# lsm9ds0-breakout.net
KiCad netlist of a schematic drawn in EAGLE
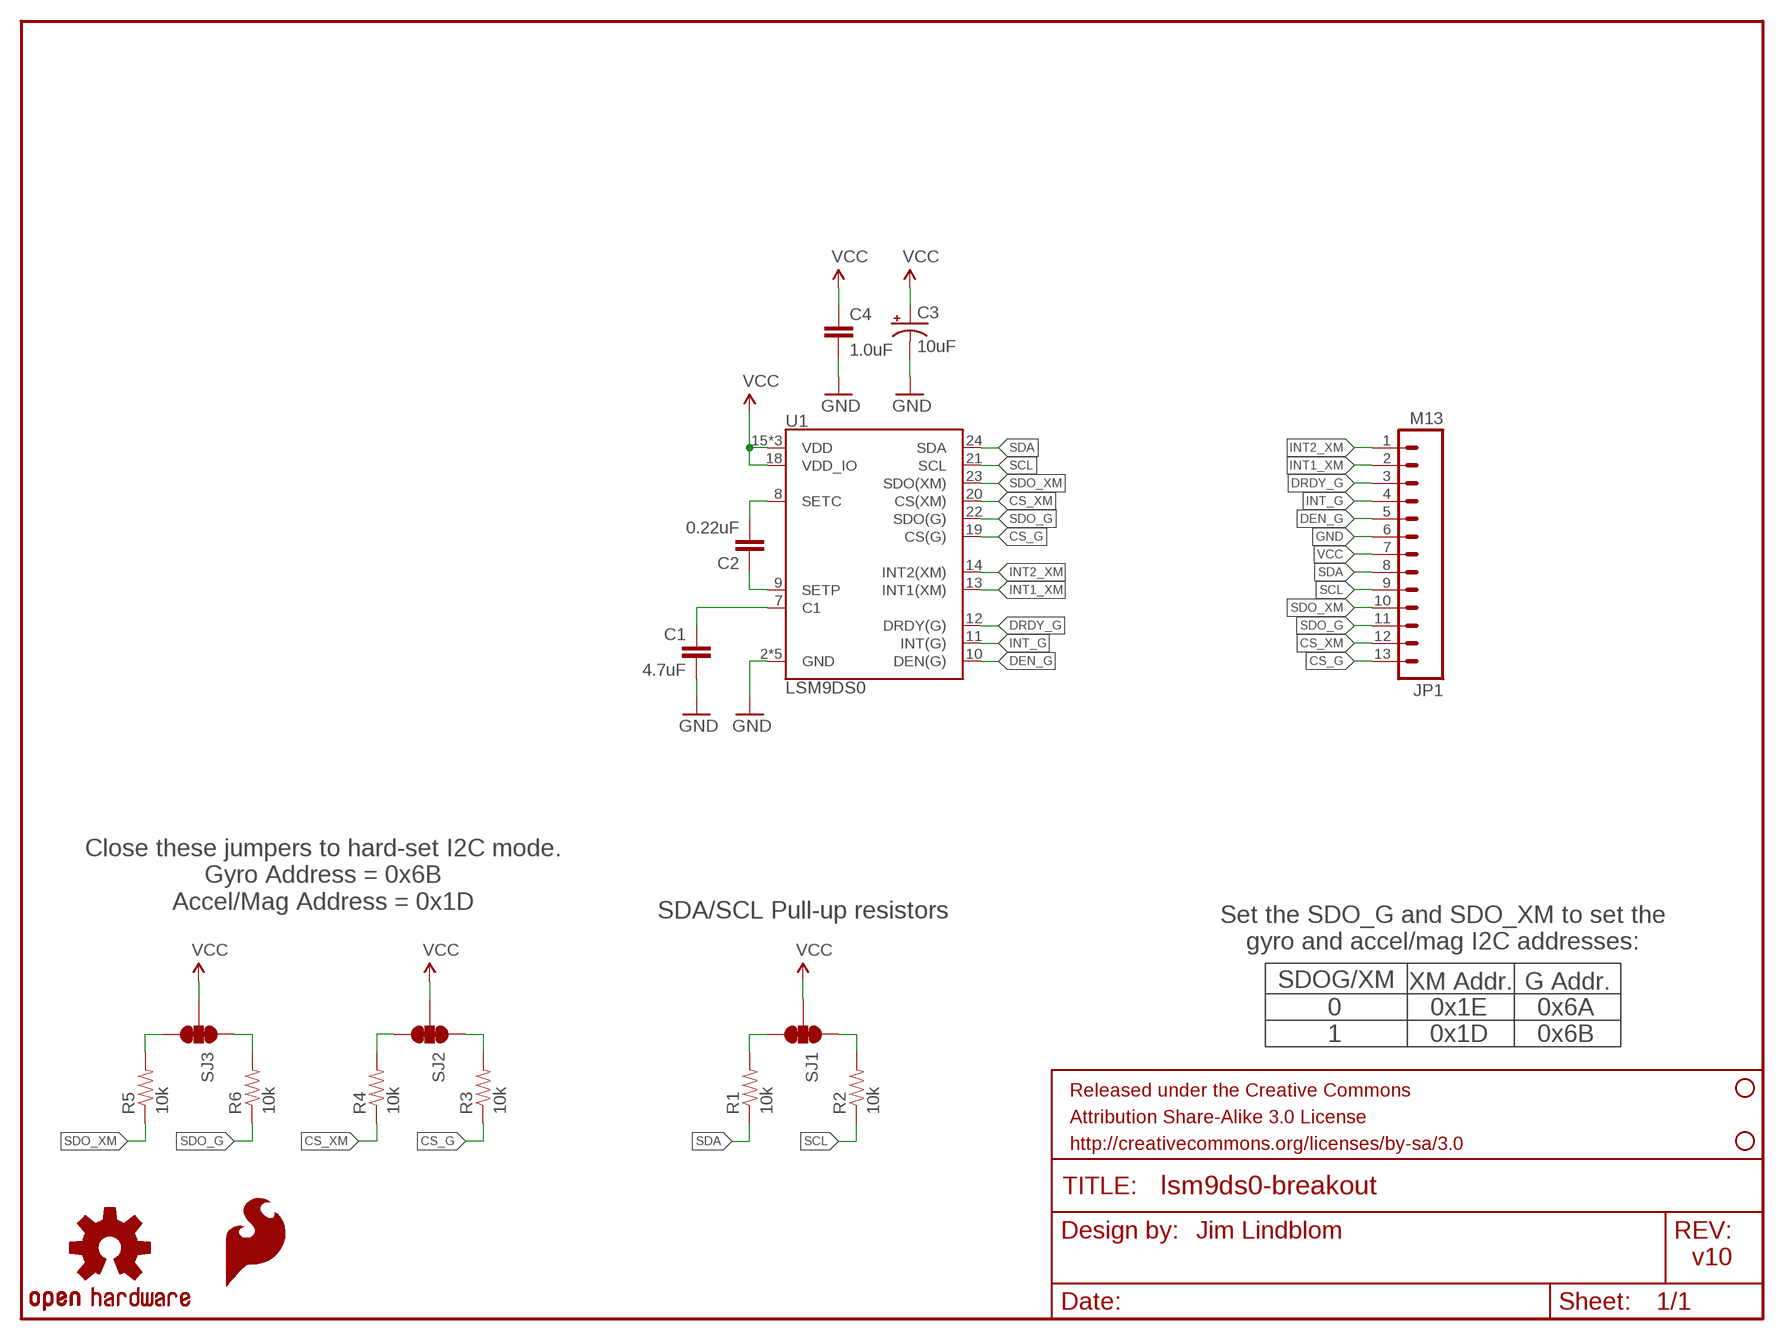
[diagram p0: schematic, sheet 1]

(export (version "E")
  (design (tool "Eeschema 10.0.6"))
  (components
    (comp (ref "C1")
      (value "4.7uF")
      (footprint "eagle-import:0603-CAP")
      (libsource (lib "eagle-import") (part "4.7UF-6.3V-10%(0603)0603"))
    )
    (comp (ref "C2")
      (value "0.22uF")
      (footprint "eagle-import:0603-CAP")
      (libsource (lib "eagle-import") (part "0.22UF-25V-10%(0603)"))
    )
    (comp (ref "C3")
      (value "10uF")
      (footprint "eagle-import:EIA3216")
      (libsource (lib "eagle-import") (part "10UF-16V-10%(TANT)"))
    )
    (comp (ref "C4")
      (value "1.0uF")
      (footprint "eagle-import:0603-CAP")
      (libsource (lib "eagle-import") (part "1.0UF-16V-10%(0603)"))
    )
    (comp (ref "FRAME1")
      (value "FRAME-LETTER")
      (footprint "eagle-import:CREATIVE_COMMONS")
      (libsource (lib "eagle-import") (part "FRAME-LETTER"))
    )
    (comp (ref "JP1")
      (value "M13")
      (footprint "eagle-import:1X13")
      (libsource (lib "eagle-import") (part "M13"))
    )
    (comp (ref "LOGO1")
      (value "OSHW-LOGOS")
      (footprint "eagle-import:OSHW-LOGO-S")
      (libsource (lib "eagle-import") (part "OSHW-LOGOS"))
    )
    (comp (ref "LOGO2")
      (value "SFE_LOGO_FLAME.1_INCH")
      (footprint "eagle-import:SFE_LOGO_FLAME_.1")
      (libsource (lib "eagle-import") (part "SFE_LOGO_FLAME.1_INCH"))
    )
    (comp (ref "LOGO3")
      (value "SFE_LOGO_FLAME.1_INCH")
      (footprint "eagle-import:SFE_LOGO_FLAME_.1")
      (libsource (lib "eagle-import") (part "SFE_LOGO_FLAME.1_INCH"))
    )
    (comp (ref "R1")
      (value "10k")
      (footprint "eagle-import:0603-RES")
      (libsource (lib "eagle-import") (part "10K-1%RES-00824"))
    )
    (comp (ref "R2")
      (value "10k")
      (footprint "eagle-import:0603-RES")
      (libsource (lib "eagle-import") (part "10K-1%RES-00824"))
    )
    (comp (ref "R3")
      (value "10k")
      (footprint "eagle-import:0603-RES")
      (libsource (lib "eagle-import") (part "10K-1%RES-00824"))
    )
    (comp (ref "R4")
      (value "10k")
      (footprint "eagle-import:0603-RES")
      (libsource (lib "eagle-import") (part "10K-1%RES-00824"))
    )
    (comp (ref "R5")
      (value "10k")
      (footprint "eagle-import:0603-RES")
      (libsource (lib "eagle-import") (part "10K-1%RES-00824"))
    )
    (comp (ref "R6")
      (value "10k")
      (footprint "eagle-import:0603-RES")
      (libsource (lib "eagle-import") (part "10K-1%RES-00824"))
    )
    (comp (ref "SJ1")
      (value "SOLDERJUMPER_2WAYS")
      (footprint "eagle-import:SJ_3")
      (libsource (lib "eagle-import") (part "SOLDERJUMPER_2WAYS"))
    )
    (comp (ref "SJ2")
      (value "SOLDERJUMPER_2WAYS")
      (footprint "eagle-import:SJ_3")
      (libsource (lib "eagle-import") (part "SOLDERJUMPER_2WAYS"))
    )
    (comp (ref "SJ3")
      (value "SOLDERJUMPER_2WAYS")
      (footprint "eagle-import:SJ_3")
      (libsource (lib "eagle-import") (part "SOLDERJUMPER_2WAYS"))
    )
    (comp (ref "STANDOFF1")
      (value "STAND-OFF")
      (footprint "eagle-import:STAND-OFF")
      (libsource (lib "eagle-import") (part "STAND-OFF"))
    )
    (comp (ref "STANDOFF2")
      (value "STAND-OFF")
      (footprint "eagle-import:STAND-OFF")
      (libsource (lib "eagle-import") (part "STAND-OFF"))
    )
    (comp (ref "U1")
      (value "LSM9DS0")
      (footprint "eagle-import:LGA-24")
      (libsource (lib "eagle-import") (part "LSM9DS0"))
    )
  )
  (nets
    (net (code "1") (name "CS_G") (class "Default")
      (node (ref "JP1") (pin "13") (pinfunction "13_13") (pintype "passive"))
      (node (ref "R3") (pin "1") (pinfunction "1_1") (pintype "passive"))
      (node (ref "U1") (pin "19") (pinfunction "CS(G)_19") (pintype "bidirectional"))
    )
    (net (code "2") (name "CS_XM") (class "Default")
      (node (ref "JP1") (pin "12") (pinfunction "12_12") (pintype "passive"))
      (node (ref "R4") (pin "1") (pinfunction "1_1") (pintype "passive"))
      (node (ref "U1") (pin "20") (pinfunction "CS(XM)_20") (pintype "bidirectional"))
    )
    (net (code "3") (name "DEN_G") (class "Default")
      (node (ref "JP1") (pin "5") (pinfunction "5_5") (pintype "passive"))
      (node (ref "U1") (pin "10") (pinfunction "DEN(G)_10") (pintype "bidirectional"))
    )
    (net (code "4") (name "DRDY_G") (class "Default")
      (node (ref "JP1") (pin "3") (pinfunction "3_3") (pintype "passive"))
      (node (ref "U1") (pin "12") (pinfunction "DRDY(G)_12") (pintype "bidirectional"))
    )
    (net (code "5") (name "GND") (class "Default")
      (node (ref "C1") (pin "2") (pinfunction "2_2") (pintype "passive"))
      (node (ref "C3") (pin "C") (pinfunction "-_C") (pintype "passive"))
      (node (ref "C4") (pin "2") (pinfunction "2_2") (pintype "passive"))
      (node (ref "JP1") (pin "6") (pinfunction "6_6") (pintype "passive"))
      (node (ref "U1") (pin "2") (pinfunction "GND_2") (pintype "bidirectional"))
      (node (ref "U1") (pin "3") (pinfunction "GND_3") (pintype "bidirectional"))
      (node (ref "U1") (pin "4") (pinfunction "GND_4") (pintype "bidirectional"))
      (node (ref "U1") (pin "5") (pinfunction "GND_5") (pintype "bidirectional"))
      (node (ref "U1") (pin "6") (pinfunction "GND_6") (pintype "bidirectional"))
    )
    (net (code "6") (name "INT1_XM") (class "Default")
      (node (ref "JP1") (pin "2") (pinfunction "2_2") (pintype "passive"))
      (node (ref "U1") (pin "13") (pinfunction "INT1(XM)_13") (pintype "bidirectional"))
    )
    (net (code "7") (name "INT2_XM") (class "Default")
      (node (ref "JP1") (pin "1") (pinfunction "1_1") (pintype "passive"))
      (node (ref "U1") (pin "14") (pinfunction "INT2(XM)_14") (pintype "bidirectional"))
    )
    (net (code "8") (name "INT_G") (class "Default")
      (node (ref "JP1") (pin "4") (pinfunction "4_4") (pintype "passive"))
      (node (ref "U1") (pin "11") (pinfunction "INT(G)_11") (pintype "bidirectional"))
    )
    (net (code "9") (name "Net-(R1-Pad2)") (class "Default")
      (node (ref "R1") (pin "2") (pinfunction "2_2") (pintype "passive"))
      (node (ref "SJ1") (pin "3") (pinfunction "3_3") (pintype "passive"))
    )
    (net (code "10") (name "Net-(R2-Pad2)") (class "Default")
      (node (ref "R2") (pin "2") (pinfunction "2_2") (pintype "passive"))
      (node (ref "SJ1") (pin "1") (pinfunction "1_1") (pintype "passive"))
    )
    (net (code "11") (name "Net-(R3-Pad2)") (class "Default")
      (node (ref "R3") (pin "2") (pinfunction "2_2") (pintype "passive"))
      (node (ref "SJ2") (pin "1") (pinfunction "1_1") (pintype "passive"))
    )
    (net (code "12") (name "Net-(R4-Pad2)") (class "Default")
      (node (ref "R4") (pin "2") (pinfunction "2_2") (pintype "passive"))
      (node (ref "SJ2") (pin "3") (pinfunction "3_3") (pintype "passive"))
    )
    (net (code "13") (name "Net-(R5-Pad2)") (class "Default")
      (node (ref "R5") (pin "2") (pinfunction "2_2") (pintype "passive"))
      (node (ref "SJ3") (pin "3") (pinfunction "3_3") (pintype "passive"))
    )
    (net (code "14") (name "Net-(R6-Pad2)") (class "Default")
      (node (ref "R6") (pin "2") (pinfunction "2_2") (pintype "passive"))
      (node (ref "SJ3") (pin "1") (pinfunction "1_1") (pintype "passive"))
    )
    (net (code "15") (name "Net-(U1-C1)") (class "Default")
      (node (ref "C1") (pin "1") (pinfunction "1_1") (pintype "passive"))
      (node (ref "U1") (pin "7") (pinfunction "C1_7") (pintype "bidirectional"))
    )
    (net (code "16") (name "Net-(U1-SETC)") (class "Default")
      (node (ref "C2") (pin "2") (pinfunction "2_2") (pintype "passive"))
      (node (ref "U1") (pin "8") (pinfunction "SETC_8") (pintype "bidirectional"))
    )
    (net (code "17") (name "Net-(U1-SETP)") (class "Default")
      (node (ref "C2") (pin "1") (pinfunction "1_1") (pintype "passive"))
      (node (ref "U1") (pin "9") (pinfunction "SETP_9") (pintype "bidirectional"))
    )
    (net (code "18") (name "SCL") (class "Default")
      (node (ref "JP1") (pin "9") (pinfunction "9_9") (pintype "passive"))
      (node (ref "R2") (pin "1") (pinfunction "1_1") (pintype "passive"))
      (node (ref "U1") (pin "21") (pinfunction "SCL_21") (pintype "bidirectional"))
    )
    (net (code "19") (name "SDA") (class "Default")
      (node (ref "JP1") (pin "8") (pinfunction "8_8") (pintype "passive"))
      (node (ref "R1") (pin "1") (pinfunction "1_1") (pintype "passive"))
      (node (ref "U1") (pin "24") (pinfunction "SDA_24") (pintype "bidirectional"))
    )
    (net (code "20") (name "SDO_G") (class "Default")
      (node (ref "JP1") (pin "11") (pinfunction "11_11") (pintype "passive"))
      (node (ref "R6") (pin "1") (pinfunction "1_1") (pintype "passive"))
      (node (ref "U1") (pin "22") (pinfunction "SDO(G)_22") (pintype "bidirectional"))
    )
    (net (code "21") (name "SDO_XM") (class "Default")
      (node (ref "JP1") (pin "10") (pinfunction "10_10") (pintype "passive"))
      (node (ref "R5") (pin "1") (pinfunction "1_1") (pintype "passive"))
      (node (ref "U1") (pin "23") (pinfunction "SDO(XM)_23") (pintype "bidirectional"))
    )
    (net (code "22") (name "VCC") (class "Default")
      (node (ref "C3") (pin "A") (pinfunction "+_A") (pintype "passive"))
      (node (ref "C4") (pin "1") (pinfunction "1_1") (pintype "passive"))
      (node (ref "JP1") (pin "7") (pinfunction "7_7") (pintype "passive"))
      (node (ref "SJ1") (pin "2") (pinfunction "2_2") (pintype "passive"))
      (node (ref "SJ2") (pin "2") (pinfunction "2_2") (pintype "passive"))
      (node (ref "SJ3") (pin "2") (pinfunction "2_2") (pintype "passive"))
      (node (ref "U1") (pin "15") (pinfunction "VDD_15") (pintype "bidirectional"))
      (node (ref "U1") (pin "16") (pinfunction "VDD_16") (pintype "bidirectional"))
      (node (ref "U1") (pin "17") (pinfunction "VDD_17") (pintype "bidirectional"))
      (node (ref "U1") (pin "18") (pinfunction "VDD_IO_18") (pintype "bidirectional"))
    )
  )
)
